# BRD161001.net
KiCad netlist of a schematic drawn in EAGLE
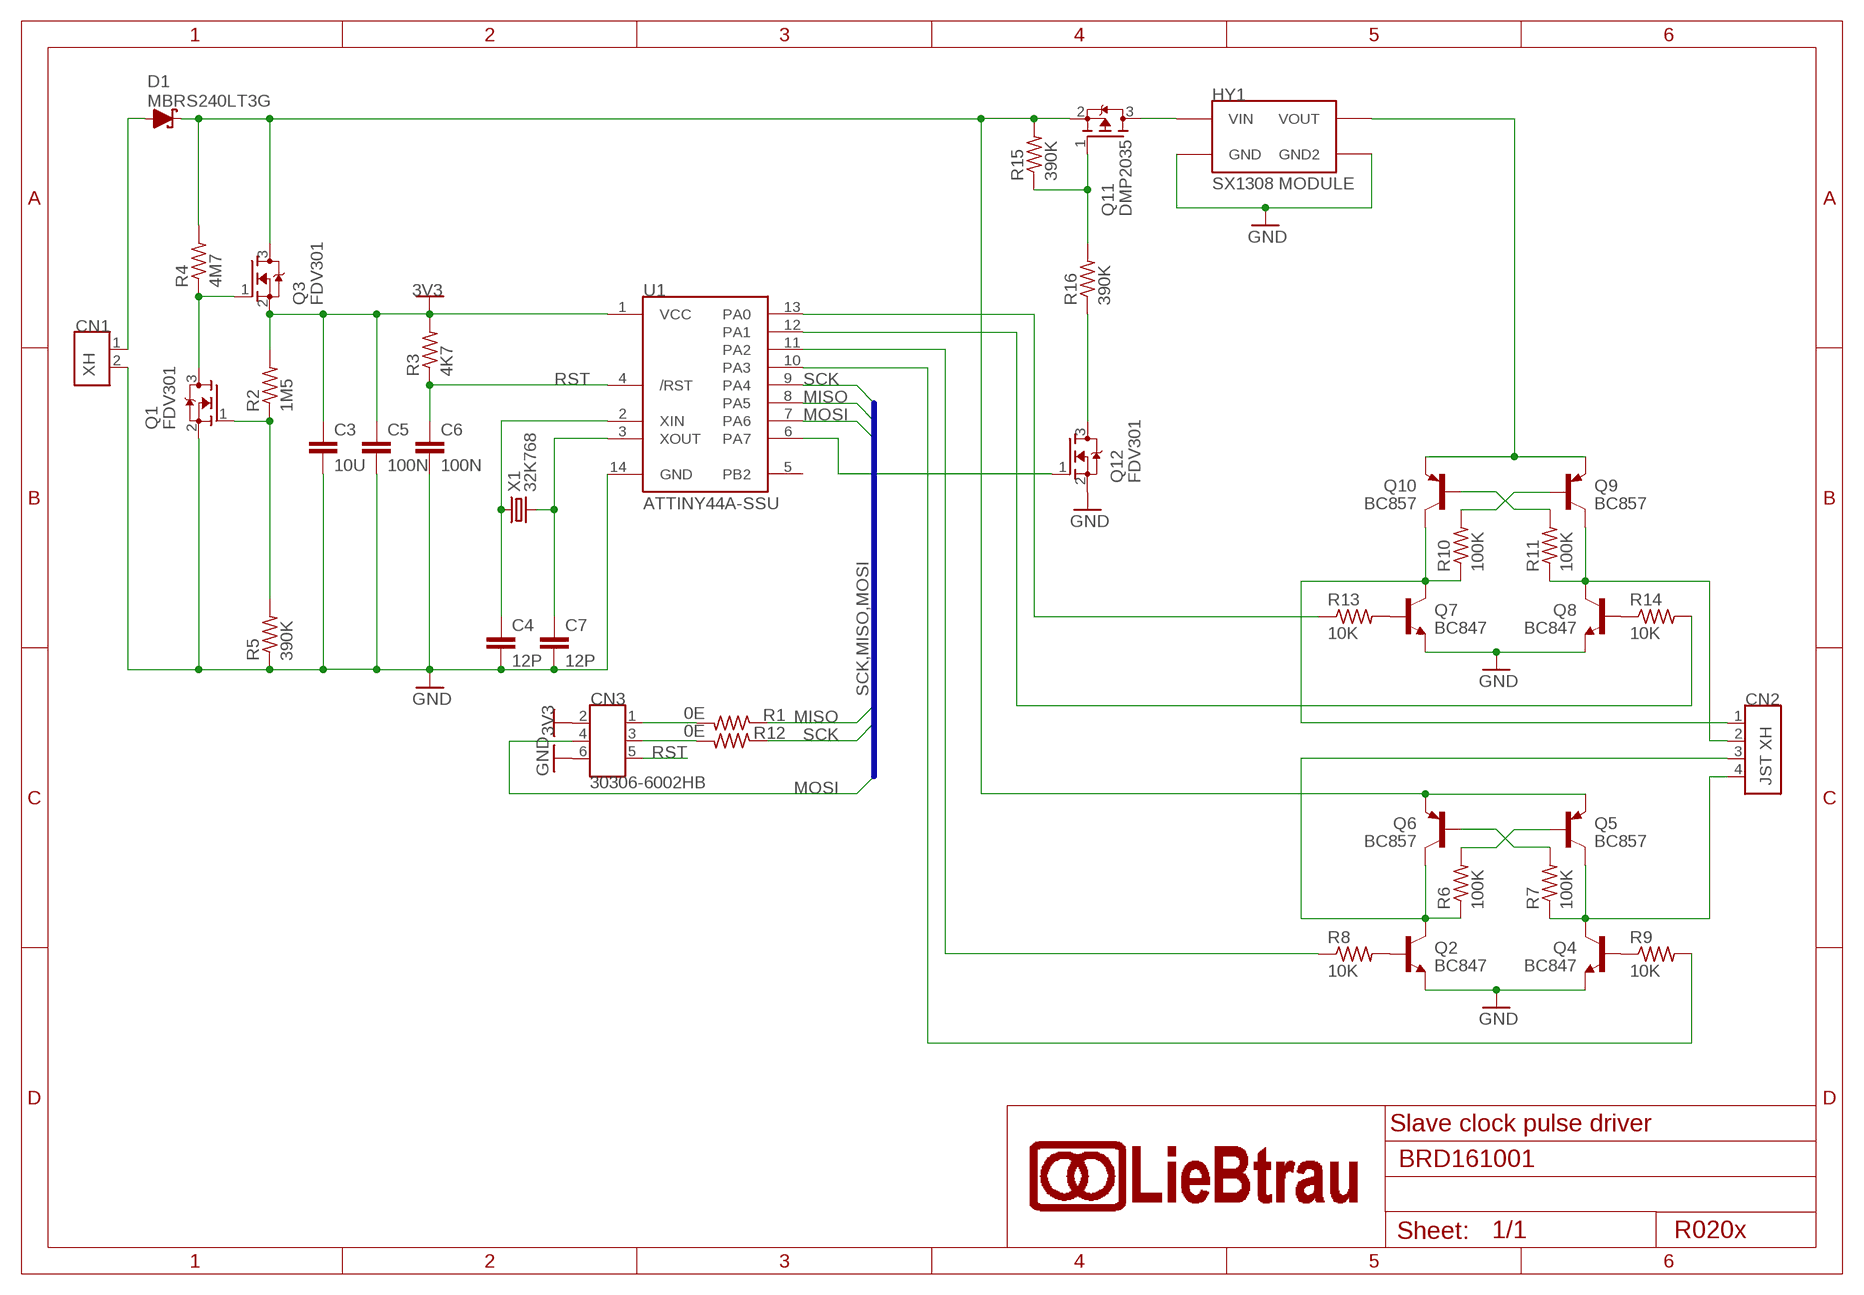
[diagram p0: schematic, sheet 1]

(export (version "E")
  (design (tool "Eeschema 10.0.6"))
  (components
    (comp (ref "C3")
      (value "10U")
      (footprint "eagle-import:CA_1206")
      (libsource (lib "eagle-import") (part "CA1206_10U_"))
    )
    (comp (ref "C4")
      (value "12P")
      (footprint "eagle-import:CA_0603")
      (libsource (lib "eagle-import") (part "CA0603_12P_"))
    )
    (comp (ref "C5")
      (value "100N")
      (footprint "eagle-import:CA_1206")
      (libsource (lib "eagle-import") (part "CA1206_100N_"))
    )
    (comp (ref "C6")
      (value "100N")
      (footprint "eagle-import:CA_1206")
      (libsource (lib "eagle-import") (part "CA1206_100N_"))
    )
    (comp (ref "C7")
      (value "12P")
      (footprint "eagle-import:CA_0603")
      (libsource (lib "eagle-import") (part "CA0603_12P_"))
    )
    (comp (ref "CN1")
      (value "XH")
      (footprint "eagle-import:CN_HDR1X2_180D_P25_JST_B2B-XH")
      (libsource (lib "eagle-import") (part "CN_2PJST_B2B-XH_JST_B2B-XH_"))
    )
    (comp (ref "CN2")
      (value "JST XH")
      (footprint "eagle-import:CN_HDR1X4_180D_P25_JST_B4B-XH")
      (libsource (lib "eagle-import") (part "CN_4PJST_B4B-XH_JST_B4B-XH_"))
    )
    (comp (ref "CN3")
      (value "30306-6002HB")
      (footprint "eagle-import:CN_HDR2X3_180D_P25_3M")
      (libsource (lib "eagle-import") (part "CN_2X3P180D_P25_3M_IDC6_"))
    )
    (comp (ref "D1")
      (value "MBRS240LT3G")
      (footprint "eagle-import:DI_DO214AA_SMB")
      (libsource (lib "eagle-import") (part "DI_SCHOTTKYDO-214AA_MBRS240_"))
    )
    (comp (ref "HY1")
      (value "SX1308 MODULE")
      (footprint "eagle-import:HY_SX1308")
      (libsource (lib "eagle-import") (part "HY_SX1308SX1308_SX1308_"))
    )
    (comp (ref "Q1")
      (value "FDV301")
      (footprint "eagle-import:SC_SOT23")
      (libsource (lib "eagle-import") (part "TR_NMOSSOT23_FDV301_"))
    )
    (comp (ref "Q2")
      (value "BC847")
      (footprint "eagle-import:SC_SOT23")
      (libsource (lib "eagle-import") (part "TR_NPNSOT23_BC847_"))
    )
    (comp (ref "Q3")
      (value "FDV301")
      (footprint "eagle-import:SC_SOT23")
      (libsource (lib "eagle-import") (part "TR_NMOSSOT23_FDV301_"))
    )
    (comp (ref "Q4")
      (value "BC847")
      (footprint "eagle-import:SC_SOT23")
      (libsource (lib "eagle-import") (part "TR_NPNSOT23_BC847_"))
    )
    (comp (ref "Q5")
      (value "BC857")
      (footprint "eagle-import:SC_SOT23")
      (libsource (lib "eagle-import") (part "TR_PNPSOT23_BC857_"))
    )
    (comp (ref "Q6")
      (value "BC857")
      (footprint "eagle-import:SC_SOT23")
      (libsource (lib "eagle-import") (part "TR_PNPSOT23_BC857_"))
    )
    (comp (ref "Q7")
      (value "BC847")
      (footprint "eagle-import:SC_SOT23")
      (libsource (lib "eagle-import") (part "TR_NPNSOT23_BC847_"))
    )
    (comp (ref "Q8")
      (value "BC847")
      (footprint "eagle-import:SC_SOT23")
      (libsource (lib "eagle-import") (part "TR_NPNSOT23_BC847_"))
    )
    (comp (ref "Q9")
      (value "BC857")
      (footprint "eagle-import:SC_SOT23")
      (libsource (lib "eagle-import") (part "TR_PNPSOT23_BC857_"))
    )
    (comp (ref "Q10")
      (value "BC857")
      (footprint "eagle-import:SC_SOT23")
      (libsource (lib "eagle-import") (part "TR_PNPSOT23_BC857_"))
    )
    (comp (ref "Q11")
      (value "DMP2035")
      (footprint "eagle-import:SC_SOT23")
      (libsource (lib "eagle-import") (part "TR_PMOSSOT23_DMP2035_"))
    )
    (comp (ref "Q12")
      (value "FDV301")
      (footprint "eagle-import:SC_SOT23")
      (libsource (lib "eagle-import") (part "TR_NMOSSOT23_FDV301_"))
    )
    (comp (ref "R1")
      (value "0E")
      (footprint "eagle-import:RE_1206")
      (libsource (lib "eagle-import") (part "RE1206_0E_"))
    )
    (comp (ref "R2")
      (value "1M5")
      (footprint "eagle-import:RE_1206")
      (libsource (lib "eagle-import") (part "RE1206_1M5_"))
    )
    (comp (ref "R3")
      (value "4K7")
      (footprint "eagle-import:RE_1206")
      (libsource (lib "eagle-import") (part "RE1206_4K7_"))
    )
    (comp (ref "R4")
      (value "4M7")
      (footprint "eagle-import:RE_1206")
      (libsource (lib "eagle-import") (part "RE1206_4M7_"))
    )
    (comp (ref "R5")
      (value "390K")
      (footprint "eagle-import:RE_1206")
      (libsource (lib "eagle-import") (part "RE1206_390K_"))
    )
    (comp (ref "R6")
      (value "100K")
      (footprint "eagle-import:RE_1206")
      (libsource (lib "eagle-import") (part "RE1206_100K_"))
    )
    (comp (ref "R7")
      (value "100K")
      (footprint "eagle-import:RE_1206")
      (libsource (lib "eagle-import") (part "RE1206_100K_"))
    )
    (comp (ref "R8")
      (value "10K")
      (footprint "eagle-import:RE_1206")
      (libsource (lib "eagle-import") (part "RE1206_10K_"))
    )
    (comp (ref "R9")
      (value "10K")
      (footprint "eagle-import:RE_1206")
      (libsource (lib "eagle-import") (part "RE1206_10K_"))
    )
    (comp (ref "R10")
      (value "100K")
      (footprint "eagle-import:RE_1206")
      (libsource (lib "eagle-import") (part "RE1206_100K_"))
    )
    (comp (ref "R11")
      (value "100K")
      (footprint "eagle-import:RE_1206")
      (libsource (lib "eagle-import") (part "RE1206_100K_"))
    )
    (comp (ref "R12")
      (value "0E")
      (footprint "eagle-import:RE_1206")
      (libsource (lib "eagle-import") (part "RE1206_0E_"))
    )
    (comp (ref "R13")
      (value "10K")
      (footprint "eagle-import:RE_1206")
      (libsource (lib "eagle-import") (part "RE1206_10K_"))
    )
    (comp (ref "R14")
      (value "10K")
      (footprint "eagle-import:RE_1206")
      (libsource (lib "eagle-import") (part "RE1206_10K_"))
    )
    (comp (ref "R15")
      (value "390K")
      (footprint "eagle-import:RE_1206")
      (libsource (lib "eagle-import") (part "RE1206_390K_"))
    )
    (comp (ref "R16")
      (value "390K")
      (footprint "eagle-import:RE_1206")
      (libsource (lib "eagle-import") (part "RE1206_390K_"))
    )
    (comp (ref "U1")
      (value "ATTINY44A-SSU")
      (footprint "eagle-import:SC_SO14")
      (libsource (lib "eagle-import") (part "IC_ATTINY44SSU_ATTINY44A_"))
    )
    (comp (ref "X1")
      (value "32K768")
      (footprint "eagle-import:XT_3215")
      (libsource (lib "eagle-import") (part "XT_32K768_32153215_32K768_"))
    )
  )
  (nets
    (net (code "1") (name "/MISO") (class "Default")
      (node (ref "R1") (pin "1") (pinfunction "1_1") (pintype "passive"))
      (node (ref "U1") (pin "8") (pinfunction "PA5_8") (pintype "bidirectional"))
    )
    (net (code "2") (name "/MOSI") (class "Default")
      (node (ref "CN3") (pin "4") (pinfunction "4_4") (pintype "bidirectional"))
      (node (ref "U1") (pin "7") (pinfunction "PA6_7") (pintype "bidirectional"))
    )
    (net (code "3") (name "/RST") (class "Default")
      (node (ref "C6") (pin "1") (pinfunction "1_1") (pintype "passive"))
      (node (ref "CN3") (pin "5") (pinfunction "5_5") (pintype "bidirectional"))
      (node (ref "R3") (pin "1") (pinfunction "1_1") (pintype "passive"))
      (node (ref "U1") (pin "4") (pinfunction "/RST_4") (pintype "bidirectional"))
    )
    (net (code "4") (name "/SCK") (class "Default")
      (node (ref "R12") (pin "1") (pinfunction "1_1") (pintype "passive"))
      (node (ref "U1") (pin "9") (pinfunction "PA4_9") (pintype "bidirectional"))
    )
    (net (code "6") (name "3V3") (class "Default")
      (node (ref "C3") (pin "1") (pinfunction "1_1") (pintype "passive"))
      (node (ref "C5") (pin "1") (pinfunction "1_1") (pintype "passive"))
      (node (ref "CN3") (pin "2") (pinfunction "2_2") (pintype "bidirectional"))
      (node (ref "Q3") (pin "2") (pinfunction "S_2") (pintype "passive"))
      (node (ref "R2") (pin "2") (pinfunction "2_2") (pintype "passive"))
      (node (ref "R3") (pin "2") (pinfunction "2_2") (pintype "passive"))
      (node (ref "U1") (pin "1") (pinfunction "VCC_1") (pintype "bidirectional"))
    )
    (net (code "7") (name "GND") (class "Default")
      (node (ref "C3") (pin "2") (pinfunction "2_2") (pintype "passive"))
      (node (ref "C4") (pin "2") (pinfunction "2_2") (pintype "passive"))
      (node (ref "C5") (pin "2") (pinfunction "2_2") (pintype "passive"))
      (node (ref "C6") (pin "2") (pinfunction "2_2") (pintype "passive"))
      (node (ref "C7") (pin "2") (pinfunction "2_2") (pintype "passive"))
      (node (ref "CN1") (pin "2") (pinfunction "2_2") (pintype "bidirectional"))
      (node (ref "CN3") (pin "6") (pinfunction "6_6") (pintype "bidirectional"))
      (node (ref "HY1") (pin "GND1") (pinfunction "GND_GND1") (pintype "bidirectional"))
      (node (ref "HY1") (pin "GND2") (pinfunction "GND2_GND2") (pintype "bidirectional"))
      (node (ref "Q1") (pin "2") (pinfunction "S_2") (pintype "passive"))
      (node (ref "Q12") (pin "2") (pinfunction "S_2") (pintype "passive"))
      (node (ref "Q2") (pin "2") (pinfunction "E_2") (pintype "passive"))
      (node (ref "Q4") (pin "2") (pinfunction "E_2") (pintype "passive"))
      (node (ref "Q7") (pin "2") (pinfunction "E_2") (pintype "passive"))
      (node (ref "Q8") (pin "2") (pinfunction "E_2") (pintype "passive"))
      (node (ref "R5") (pin "1") (pinfunction "1_1") (pintype "passive"))
      (node (ref "U1") (pin "14") (pinfunction "GND_14") (pintype "bidirectional"))
    )
    (net (code "8") (name "Net-(CN1-Pad1)") (class "Default")
      (node (ref "CN1") (pin "1") (pinfunction "1_1") (pintype "bidirectional"))
      (node (ref "D1") (pin "A") (pinfunction "A_A") (pintype "passive"))
    )
    (net (code "9") (name "Net-(CN3-Pad1)") (class "Default")
      (node (ref "CN3") (pin "1") (pinfunction "1_1") (pintype "bidirectional"))
      (node (ref "R1") (pin "2") (pinfunction "2_2") (pintype "passive"))
    )
    (net (code "10") (name "Net-(CN3-Pad3)") (class "Default")
      (node (ref "CN3") (pin "3") (pinfunction "3_3") (pintype "bidirectional"))
      (node (ref "R12") (pin "2") (pinfunction "2_2") (pintype "passive"))
    )
    (net (code "11") (name "Net-(HY1-VOUT)") (class "Default")
      (node (ref "HY1") (pin "OUT") (pinfunction "VOUT_OUT") (pintype "bidirectional"))
      (node (ref "Q10") (pin "2") (pinfunction "E_2") (pintype "passive"))
      (node (ref "Q9") (pin "2") (pinfunction "E_2") (pintype "passive"))
    )
    (net (code "12") (name "Net-(Q1-D)") (class "Default")
      (node (ref "Q1") (pin "3") (pinfunction "D_3") (pintype "passive"))
      (node (ref "Q3") (pin "1") (pinfunction "G_1") (pintype "passive"))
      (node (ref "R4") (pin "1") (pinfunction "1_1") (pintype "passive"))
    )
    (net (code "13") (name "Net-(Q1-G)") (class "Default")
      (node (ref "Q1") (pin "1") (pinfunction "G_1") (pintype "passive"))
      (node (ref "R2") (pin "1") (pinfunction "1_1") (pintype "passive"))
      (node (ref "R5") (pin "2") (pinfunction "2_2") (pintype "passive"))
    )
    (net (code "14") (name "Net-(Q2-B)") (class "Default")
      (node (ref "Q2") (pin "1") (pinfunction "B_1") (pintype "passive"))
      (node (ref "R8") (pin "2") (pinfunction "2_2") (pintype "passive"))
    )
    (net (code "15") (name "Net-(Q2-C)") (class "Default")
      (node (ref "CN2") (pin "3") (pinfunction "3_3") (pintype "bidirectional"))
      (node (ref "Q2") (pin "3") (pinfunction "C_3") (pintype "passive"))
      (node (ref "Q6") (pin "3") (pinfunction "C_3") (pintype "passive"))
      (node (ref "R6") (pin "1") (pinfunction "1_1") (pintype "passive"))
    )
    (net (code "16") (name "Net-(Q4-B)") (class "Default")
      (node (ref "Q4") (pin "1") (pinfunction "B_1") (pintype "passive"))
      (node (ref "R9") (pin "1") (pinfunction "1_1") (pintype "passive"))
    )
    (net (code "17") (name "Net-(Q4-C)") (class "Default")
      (node (ref "CN2") (pin "4") (pinfunction "4_4") (pintype "bidirectional"))
      (node (ref "Q4") (pin "3") (pinfunction "C_3") (pintype "passive"))
      (node (ref "Q5") (pin "3") (pinfunction "C_3") (pintype "passive"))
      (node (ref "R7") (pin "1") (pinfunction "1_1") (pintype "passive"))
    )
    (net (code "18") (name "Net-(Q5-B)") (class "Default")
      (node (ref "Q5") (pin "1") (pinfunction "B_1") (pintype "passive"))
      (node (ref "R6") (pin "2") (pinfunction "2_2") (pintype "passive"))
    )
    (net (code "19") (name "Net-(Q6-B)") (class "Default")
      (node (ref "Q6") (pin "1") (pinfunction "B_1") (pintype "passive"))
      (node (ref "R7") (pin "2") (pinfunction "2_2") (pintype "passive"))
    )
    (net (code "20") (name "Net-(Q7-B)") (class "Default")
      (node (ref "Q7") (pin "1") (pinfunction "B_1") (pintype "passive"))
      (node (ref "R13") (pin "2") (pinfunction "2_2") (pintype "passive"))
    )
    (net (code "21") (name "Net-(Q8-B)") (class "Default")
      (node (ref "Q8") (pin "1") (pinfunction "B_1") (pintype "passive"))
      (node (ref "R14") (pin "1") (pinfunction "1_1") (pintype "passive"))
    )
    (net (code "22") (name "Net-(Q8-C)") (class "Default")
      (node (ref "CN2") (pin "2") (pinfunction "2_2") (pintype "bidirectional"))
      (node (ref "Q8") (pin "3") (pinfunction "C_3") (pintype "passive"))
      (node (ref "Q9") (pin "3") (pinfunction "C_3") (pintype "passive"))
      (node (ref "R11") (pin "1") (pinfunction "1_1") (pintype "passive"))
    )
    (net (code "23") (name "Net-(Q9-B)") (class "Default")
      (node (ref "Q9") (pin "1") (pinfunction "B_1") (pintype "passive"))
      (node (ref "R10") (pin "2") (pinfunction "2_2") (pintype "passive"))
    )
    (net (code "24") (name "Net-(Q10-B)") (class "Default")
      (node (ref "Q10") (pin "1") (pinfunction "B_1") (pintype "passive"))
      (node (ref "R11") (pin "2") (pinfunction "2_2") (pintype "passive"))
    )
    (net (code "25") (name "Net-(Q10-C)") (class "Default")
      (node (ref "CN2") (pin "1") (pinfunction "1_1") (pintype "bidirectional"))
      (node (ref "Q10") (pin "3") (pinfunction "C_3") (pintype "passive"))
      (node (ref "Q7") (pin "3") (pinfunction "C_3") (pintype "passive"))
      (node (ref "R10") (pin "1") (pinfunction "1_1") (pintype "passive"))
    )
    (net (code "26") (name "Net-(Q11-D)") (class "Default")
      (node (ref "HY1") (pin "VIN") (pinfunction "VIN_VIN") (pintype "bidirectional"))
      (node (ref "Q11") (pin "3") (pinfunction "D_3") (pintype "passive"))
    )
    (net (code "27") (name "Net-(Q11-G)") (class "Default")
      (node (ref "Q11") (pin "1") (pinfunction "G_1") (pintype "passive"))
      (node (ref "R15") (pin "1") (pinfunction "1_1") (pintype "passive"))
      (node (ref "R16") (pin "2") (pinfunction "2_2") (pintype "passive"))
    )
    (net (code "28") (name "Net-(Q11-S)") (class "Default")
      (node (ref "D1") (pin "C") (pinfunction "C_C") (pintype "passive"))
      (node (ref "Q11") (pin "2") (pinfunction "S_2") (pintype "passive"))
      (node (ref "Q3") (pin "3") (pinfunction "D_3") (pintype "passive"))
      (node (ref "Q5") (pin "2") (pinfunction "E_2") (pintype "passive"))
      (node (ref "Q6") (pin "2") (pinfunction "E_2") (pintype "passive"))
      (node (ref "R15") (pin "2") (pinfunction "2_2") (pintype "passive"))
      (node (ref "R4") (pin "2") (pinfunction "2_2") (pintype "passive"))
    )
    (net (code "29") (name "Net-(Q12-D)") (class "Default")
      (node (ref "Q12") (pin "3") (pinfunction "D_3") (pintype "passive"))
      (node (ref "R16") (pin "1") (pinfunction "1_1") (pintype "passive"))
    )
    (net (code "30") (name "Net-(Q12-G)") (class "Default")
      (node (ref "Q12") (pin "1") (pinfunction "G_1") (pintype "passive"))
      (node (ref "U1") (pin "6") (pinfunction "PA7_6") (pintype "bidirectional"))
    )
    (net (code "31") (name "Net-(U1-PA0)") (class "Default")
      (node (ref "R13") (pin "1") (pinfunction "1_1") (pintype "passive"))
      (node (ref "U1") (pin "13") (pinfunction "PA0_13") (pintype "bidirectional"))
    )
    (net (code "32") (name "Net-(U1-PA1)") (class "Default")
      (node (ref "R14") (pin "2") (pinfunction "2_2") (pintype "passive"))
      (node (ref "U1") (pin "12") (pinfunction "PA1_12") (pintype "bidirectional"))
    )
    (net (code "33") (name "Net-(U1-PA2)") (class "Default")
      (node (ref "R8") (pin "1") (pinfunction "1_1") (pintype "passive"))
      (node (ref "U1") (pin "11") (pinfunction "PA2_11") (pintype "bidirectional"))
    )
    (net (code "34") (name "Net-(U1-PA3)") (class "Default")
      (node (ref "R9") (pin "2") (pinfunction "2_2") (pintype "passive"))
      (node (ref "U1") (pin "10") (pinfunction "PA3_10") (pintype "bidirectional"))
    )
    (net (code "35") (name "Net-(U1-XIN)") (class "Default")
      (node (ref "C4") (pin "1") (pinfunction "1_1") (pintype "passive"))
      (node (ref "U1") (pin "2") (pinfunction "XIN_2") (pintype "bidirectional"))
      (node (ref "X1") (pin "1") (pinfunction "1_1") (pintype "passive"))
    )
    (net (code "36") (name "Net-(U1-XOUT)") (class "Default")
      (node (ref "C7") (pin "1") (pinfunction "1_1") (pintype "passive"))
      (node (ref "U1") (pin "3") (pinfunction "XOUT_3") (pintype "bidirectional"))
      (node (ref "X1") (pin "2") (pinfunction "2_2") (pintype "passive"))
    )
    (net (code "37") (name "unconnected-(U1-PB2-Pad5)") (class "Default")
      (node (ref "U1") (pin "5") (pinfunction "PB2_5") (pintype "bidirectional"))
    )
  )
)
